# DB10005_TopLevel.net
KiCad netlist of a schematic drawn in Altium Designer
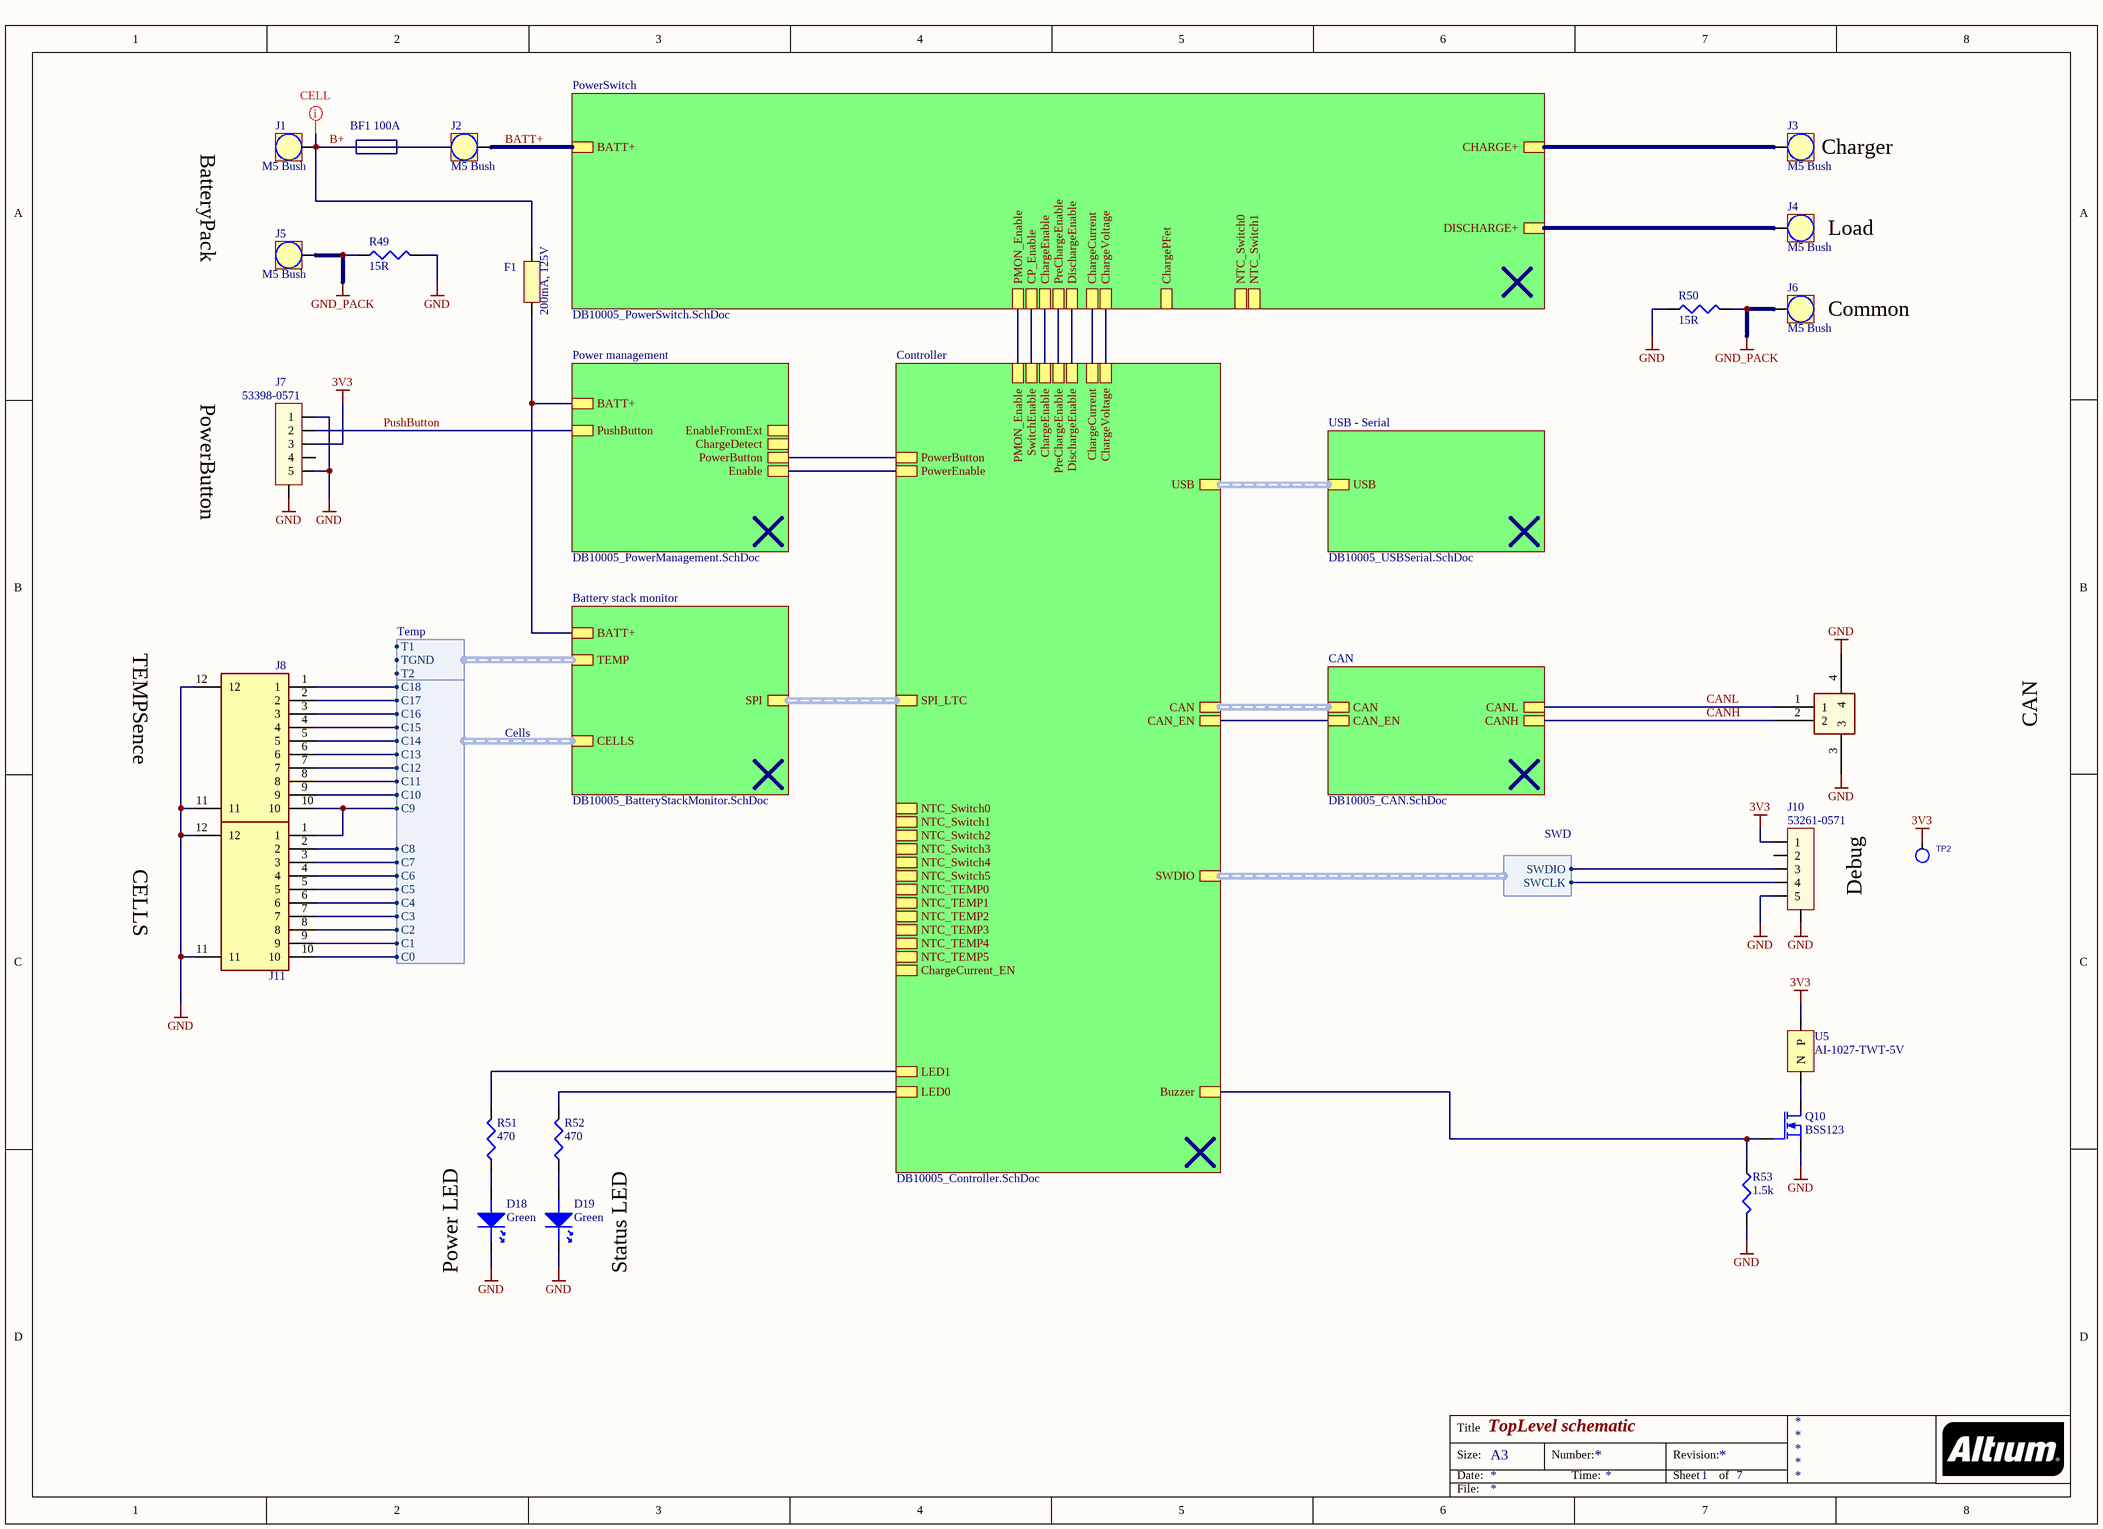
[diagram p0: DB10005_TopLevel.SchDoc]

(export (version "E")
  (design (tool "Eeschema 10.0.6"))
  (components
    (comp (ref "D18")
      (value "Green")
      (footprint "D-0805")
      (description "Led, Green, Li:12mcd, Vf:2.2V, If:0.02A")
      (libsource (lib "AR_Misc") (part "KP-2012SGC"))
    )
    (comp (ref "D19")
      (value "Green")
      (footprint "D-0805")
      (description "Led, Green, Li:12mcd, Vf:2.2V, If:0.02A")
      (libsource (lib "AR_Misc") (part "KP-2012SGC"))
    )
    (comp (ref "F1")
      (value "200mA, 125V")
      (footprint "F1206")
      (description "Fuse, Slow Blow, 200 mA, 125 VAC, 125 VDC")
      (libsource (lib "AR_Misc") (part "0466.200NR"))
    )
    (comp (ref "J1")
      (value "M5 Bush")
      (footprint "7460408_HAL Surface")
      (description "Bush with Circumference M5")
      (libsource (lib "AR_Connectors") (part "7460408"))
    )
    (comp (ref "J2")
      (value "M5 Bush")
      (footprint "7460408_HAL Surface")
      (description "Bush with Circumference M5")
      (libsource (lib "AR_Connectors") (part "7460408"))
    )
    (comp (ref "J3")
      (value "M5 Bush")
      (footprint "7460408_HAL Surface")
      (description "Bush with Circumference M5")
      (libsource (lib "") (part "7460408_1"))
    )
    (comp (ref "J4")
      (value "M5 Bush")
      (footprint "7460408_HAL Surface")
      (description "Bush with Circumference M5")
      (libsource (lib "") (part "7460408_1"))
    )
    (comp (ref "J5")
      (value "M5 Bush")
      (footprint "7460408_HAL Surface")
      (description "Bush with Circumference M5")
      (libsource (lib "AR_Connectors") (part "7460408"))
    )
    (comp (ref "J6")
      (value "M5 Bush")
      (footprint "7460408_HAL Surface")
      (description "Bush with Circumference M5")
      (libsource (lib "") (part "7460408_2"))
    )
    (comp (ref "J7")
      (value "53398-0571")
      (footprint "53398-0571")
      (description "PicoBlade 53398 Series, 5Pin, Right Angle")
      (libsource (lib "AR_Connectors") (part "53398-0571"))
    )
    (comp (ref "J8")
      (value "S10B-PH-SM4-TB_LF__SN_")
      (footprint "S10B-PH-SM4-TB")
      (description "Connector")
      (fields
        (field (name "MANUFACTURER_PART_NUMBER") "S10B-PH-SM4-TB(LF)(SN)")
        (field (name "MOUSER PART NUMBER") "306-S10BPHSM4TBLFSN")
      )
      (libsource (lib "DB10005_DieBieMS") (part "S10B-PH-SM4-TB_LF__SN_"))
    )
    (comp (ref "J9")
      (value "1.25-2PWTDK")
      (footprint "BM02B-GHS-TBT_1")
      (libsource (lib "DB10005_DieBieMS") (part "1.25-2PWTDK"))
    )
    (comp (ref "J10")
      (value "53261-0571")
      (footprint "53261-0571")
      (description "PicoBlade 53261 Series, 5Pin, Right Angle")
      (libsource (lib "AR_Connectors") (part "53261-0571"))
    )
    (comp (ref "J11")
      (value "S10B-PH-SM4-TB_LF__SN_")
      (footprint "S10B-PH-SM4-TB")
      (description "Connector")
      (fields
        (field (name "MANUFACTURER_PART_NUMBER") "S10B-PH-SM4-TB(LF)(SN)")
        (field (name "MOUSER PART NUMBER") "306-S10BPHSM4TBLFSN")
      )
      (libsource (lib "DB10005_DieBieMS") (part "S10B-PH-SM4-TB_LF__SN_"))
    )
    (comp (ref "Q10")
      (value "BSS123")
      (footprint "SOT-23")
      (description "Mosfet, N-channel, Vds:100V, Id:0.15A, Vgs-th:2.8V, Rds-on:3.5ohm")
      (libsource (lib "AR_Mosfets") (part "BSS123"))
    )
    (comp (ref "R49")
      (value "15R")
      (footprint "2512")
      (description "Resistor, 15R, 1%, 2W, 200V, 200PPM, 2512")
      (libsource (lib "AR_Resistors_SMD") (part "15/2512/2W/250V"))
    )
    (comp (ref "R50")
      (value "15R")
      (footprint "2512")
      (description "Resistor, 15R, 1%, 2W, 200V, 200PPM, 2512")
      (libsource (lib "AR_Resistors_SMD") (part "15/2512/2W/250V"))
    )
    (comp (ref "R51")
      (value "470")
      (footprint "0402")
      (description "Resistor, 470, 1%, 0.0625W, 50V, 100PPM, 0402")
      (libsource (lib "AR_Resistors_SMD") (part "470/0402/0063W/50V"))
    )
    (comp (ref "R52")
      (value "470")
      (footprint "0402")
      (description "Resistor, 470, 1%, 0.0625W, 50V, 100PPM, 0402")
      (libsource (lib "AR_Resistors_SMD") (part "470/0402/0063W/50V"))
    )
    (comp (ref "R53")
      (value "1.5k")
      (footprint "0402")
      (description "Resistor, 1.5k, 0.1%, 0.0625W, 50V, 100PPM, 0402")
      (libsource (lib "AR_Resistors_SMD") (part "1.5k/0402/0063W/50V"))
    )
    (comp (ref "TP2")
      (value "1.3TP")
      (footprint "TP2-1.3MM")
      (description "1.3mm")
      (libsource (lib "AR_Misc") (part "TESTPT4"))
    )
    (comp (ref "U5")
      (value "AI-1027-TWT-5V")
      (footprint "AI-1027-TWT")
      (description "EM 5VDC 2300Hz 82dBA Continuous Top Fire")
      (libsource (lib "AR_Misc") (part "AI-1027-TWT-5V-2-R"))
    )
  )
  (nets
    (net (code "4") (name "/B+") (class "Default")
      (node (ref "F1") (pin "2") (pinfunction "2_2") (pintype "passive"))
      (node (ref "J1") (pin "1") (pinfunction "1_1") (pintype "passive"))
    )
    (net (code "5") (name "/BATT+") (class "Default")
      (node (ref "J2") (pin "1") (pinfunction "1_1") (pintype "passive"))
    )
    (net (code "6") (name "/BATT+_1") (class "Default")
      (node (ref "F1") (pin "1") (pinfunction "1_1") (pintype "passive"))
    )
    (net (code "7") (name "/Buzzer") (class "Default")
      (node (ref "Q10") (pin "G") (pinfunction "G_G") (pintype "passive"))
      (node (ref "R53") (pin "1") (pinfunction "1_1") (pintype "passive"))
    )
    (net (code "8") (name "/C0") (class "Default")
      (node (ref "J11") (pin "10") (pinfunction "10_10") (pintype "passive"))
    )
    (net (code "9") (name "/C1") (class "Default")
      (node (ref "J11") (pin "9") (pinfunction "9_9") (pintype "passive"))
    )
    (net (code "10") (name "/C2") (class "Default")
      (node (ref "J11") (pin "8") (pinfunction "8_8") (pintype "passive"))
    )
    (net (code "11") (name "/C3") (class "Default")
      (node (ref "J11") (pin "7") (pinfunction "7_7") (pintype "passive"))
    )
    (net (code "12") (name "/C4") (class "Default")
      (node (ref "J11") (pin "6") (pinfunction "6_6") (pintype "passive"))
    )
    (net (code "13") (name "/C5") (class "Default")
      (node (ref "J11") (pin "5") (pinfunction "5_5") (pintype "passive"))
    )
    (net (code "14") (name "/C6") (class "Default")
      (node (ref "J11") (pin "4") (pinfunction "4_4") (pintype "passive"))
    )
    (net (code "15") (name "/C7") (class "Default")
      (node (ref "J11") (pin "3") (pinfunction "3_3") (pintype "passive"))
    )
    (net (code "16") (name "/C8") (class "Default")
      (node (ref "J11") (pin "2") (pinfunction "2_2") (pintype "passive"))
    )
    (net (code "17") (name "/C9") (class "Default")
      (node (ref "J11") (pin "1") (pinfunction "1_1") (pintype "passive"))
      (node (ref "J8") (pin "10") (pinfunction "10_10") (pintype "passive"))
    )
    (net (code "18") (name "/C10") (class "Default")
      (node (ref "J8") (pin "9") (pinfunction "9_9") (pintype "passive"))
    )
    (net (code "19") (name "/C11") (class "Default")
      (node (ref "J8") (pin "8") (pinfunction "8_8") (pintype "passive"))
    )
    (net (code "20") (name "/C12") (class "Default")
      (node (ref "J8") (pin "7") (pinfunction "7_7") (pintype "passive"))
    )
    (net (code "21") (name "/C13") (class "Default")
      (node (ref "J8") (pin "6") (pinfunction "6_6") (pintype "passive"))
    )
    (net (code "22") (name "/C14") (class "Default")
      (node (ref "J8") (pin "5") (pinfunction "5_5") (pintype "passive"))
    )
    (net (code "23") (name "/C15") (class "Default")
      (node (ref "J8") (pin "4") (pinfunction "4_4") (pintype "passive"))
    )
    (net (code "24") (name "/C16") (class "Default")
      (node (ref "J8") (pin "3") (pinfunction "3_3") (pintype "passive"))
    )
    (net (code "25") (name "/C17") (class "Default")
      (node (ref "J8") (pin "2") (pinfunction "2_2") (pintype "passive"))
    )
    (net (code "26") (name "/C18") (class "Default")
      (node (ref "J8") (pin "1") (pinfunction "1_1") (pintype "passive"))
    )
    (net (code "27") (name "/CANH") (class "Default")
      (node (ref "J9") (pin "2") (pinfunction "2_2") (pintype "passive"))
    )
    (net (code "28") (name "/CANL") (class "Default")
      (node (ref "J9") (pin "1") (pinfunction "1_1") (pintype "passive"))
    )
    (net (code "31") (name "/CHARGE+") (class "Default")
      (node (ref "J3") (pin "1") (pinfunction "1_1") (pintype "passive"))
    )
    (net (code "39") (name "/DISCHARGE+") (class "Default")
      (node (ref "J4") (pin "1") (pinfunction "1_1") (pintype "passive"))
    )
    (net (code "43") (name "/LED0") (class "Default")
      (node (ref "R52") (pin "2") (pinfunction "2_2") (pintype "passive"))
    )
    (net (code "44") (name "/LED1") (class "Default")
      (node (ref "R51") (pin "2") (pinfunction "2_2") (pintype "passive"))
    )
    (net (code "62") (name "/PushButton") (class "Default")
      (node (ref "J7") (pin "2") (pinfunction "2_2") (pintype "passive"))
    )
    (net (code "64") (name "/SWCLK") (class "Default")
      (node (ref "J10") (pin "4") (pinfunction "4_4") (pintype "passive"))
    )
    (net (code "65") (name "/SWDIO") (class "Default")
      (node (ref "J10") (pin "3") (pinfunction "3_3") (pintype "passive"))
    )
    (net (code "70") (name "3V3") (class "Default")
      (node (ref "J10") (pin "1") (pinfunction "1_1") (pintype "passive"))
      (node (ref "J7") (pin "3") (pinfunction "3_3") (pintype "passive"))
      (node (ref "TP2") (pin "1") (pinfunction "TP_1") (pintype "passive"))
      (node (ref "U5") (pin "P") (pinfunction "P_P") (pintype "passive"))
    )
    (net (code "71") (name "GND") (class "Default")
      (node (ref "D18") (pin "K") (pinfunction "K_K") (pintype "passive"))
      (node (ref "D19") (pin "K") (pinfunction "K_K") (pintype "passive"))
      (node (ref "J10") (pin "0") (pinfunction "SHLD_0") (pintype "passive"))
      (node (ref "J10") (pin "5") (pinfunction "5_5") (pintype "passive"))
      (node (ref "J11") (pin "11") (pinfunction "11_11") (pintype "passive"))
      (node (ref "J11") (pin "12") (pinfunction "12_12") (pintype "passive"))
      (node (ref "J7") (pin "0") (pinfunction "SHLD_0") (pintype "passive"))
      (node (ref "J7") (pin "1") (pinfunction "1_1") (pintype "passive"))
      (node (ref "J7") (pin "5") (pinfunction "5_5") (pintype "passive"))
      (node (ref "J8") (pin "11") (pinfunction "11_11") (pintype "passive"))
      (node (ref "J8") (pin "12") (pinfunction "12_12") (pintype "passive"))
      (node (ref "J9") (pin "3") (pinfunction "3_3") (pintype "passive"))
      (node (ref "J9") (pin "4") (pinfunction "4_4") (pintype "passive"))
      (node (ref "Q10") (pin "S") (pinfunction "S_S") (pintype "passive"))
      (node (ref "R49") (pin "2") (pinfunction "2_2") (pintype "passive"))
      (node (ref "R50") (pin "2") (pinfunction "2_2") (pintype "passive"))
      (node (ref "R53") (pin "2") (pinfunction "2_2") (pintype "passive"))
    )
    (net (code "72") (name "GND_PACK") (class "Default")
      (node (ref "J5") (pin "1") (pinfunction "1_1") (pintype "passive"))
      (node (ref "J6") (pin "1") (pinfunction "1_1") (pintype "passive"))
      (node (ref "R49") (pin "1") (pinfunction "1_1") (pintype "passive"))
      (node (ref "R50") (pin "1") (pinfunction "1_1") (pintype "passive"))
    )
    (net (code "73") (name "Net-(D18-PadA)") (class "Default")
      (node (ref "D18") (pin "A") (pinfunction "A_A") (pintype "passive"))
      (node (ref "R51") (pin "1") (pinfunction "1_1") (pintype "passive"))
    )
    (net (code "74") (name "Net-(D19-PadA)") (class "Default")
      (node (ref "D19") (pin "A") (pinfunction "A_A") (pintype "passive"))
      (node (ref "R52") (pin "1") (pinfunction "1_1") (pintype "passive"))
    )
    (net (code "75") (name "Net-(Q10-PadD)") (class "Default")
      (node (ref "Q10") (pin "D") (pinfunction "D_D") (pintype "passive"))
      (node (ref "U5") (pin "N") (pinfunction "N_N") (pintype "passive"))
    )
    (net (code "76") (name "unconnected-(J7-Pad4)") (class "Default")
      (node (ref "J7") (pin "4") (pinfunction "4_4") (pintype "passive"))
    )
    (net (code "77") (name "unconnected-(J10-Pad2)") (class "Default")
      (node (ref "J10") (pin "2") (pinfunction "2_2") (pintype "passive"))
    )
  )
)
